# 8LedBoard.net
KiCad netlist of a schematic drawn in EAGLE
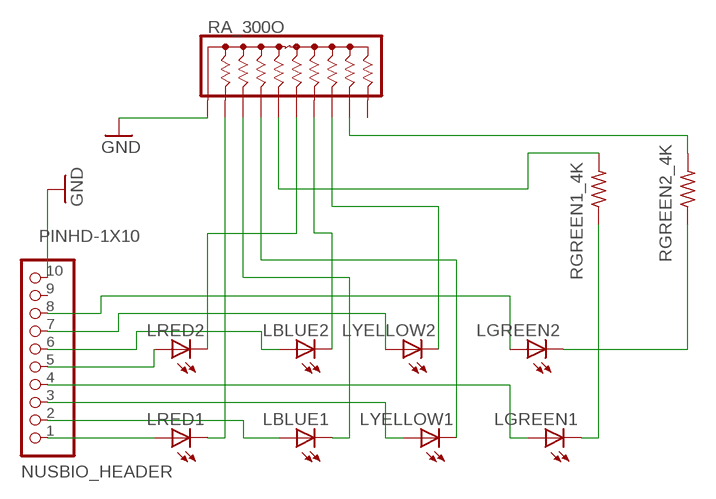
[diagram p0: schematic, sheet 1]

(export (version "E")
  (design (tool "Eeschema 10.0.6"))
  (components
    (comp (ref "LBLUE1")
      (value "LED5MM")
      (footprint "eagle-import:LED5MM")
      (libsource (lib "eagle-import") (part "LED5MM"))
    )
    (comp (ref "LBLUE2")
      (value "LED5MM")
      (footprint "eagle-import:LED5MM")
      (libsource (lib "eagle-import") (part "LED5MM"))
    )
    (comp (ref "LGREEN1")
      (value "LED5MM")
      (footprint "eagle-import:LED5MM")
      (libsource (lib "eagle-import") (part "LED5MM"))
    )
    (comp (ref "LGREEN2")
      (value "LED5MM")
      (footprint "eagle-import:LED5MM")
      (libsource (lib "eagle-import") (part "LED5MM"))
    )
    (comp (ref "LRED1")
      (value "LED5MM")
      (footprint "eagle-import:LED5MM")
      (libsource (lib "eagle-import") (part "LED5MM"))
    )
    (comp (ref "LRED2")
      (value "LED5MM")
      (footprint "eagle-import:LED5MM")
      (libsource (lib "eagle-import") (part "LED5MM"))
    )
    (comp (ref "LYELLOW1")
      (value "LED5MM")
      (footprint "eagle-import:LED5MM")
      (libsource (lib "eagle-import") (part "LED5MM"))
    )
    (comp (ref "LYELLOW2")
      (value "LED5MM")
      (footprint "eagle-import:LED5MM")
      (libsource (lib "eagle-import") (part "LED5MM"))
    )
    (comp (ref "NUSBIO_HEADER")
      (value "PINHD-1X10")
      (footprint "eagle-import:1X10-BIG")
      (libsource (lib "eagle-import") (part "PINHD-1X10"))
    )
    (comp (ref "RA_300O")
      (value "4610X")
      (footprint "eagle-import:SIP10")
      (libsource (lib "eagle-import") (part "4610X"))
    )
    (comp (ref "RGREEN1_4K")
      (value "R-US_0207/10")
      (footprint "eagle-import:0207_10")
      (libsource (lib "eagle-import") (part "R-US_0207/10"))
    )
    (comp (ref "RGREEN2_4K")
      (value "R-US_0207/10")
      (footprint "eagle-import:0207_10")
      (libsource (lib "eagle-import") (part "R-US_0207/10"))
    )
  )
  (nets
    (net (code "1") (name "GND") (class "Default")
      (node (ref "NUSBIO_HEADER") (pin "10") (pinfunction "10_10") (pintype "passive"))
      (node (ref "RA_300O") (pin "1") (pinfunction "1_1") (pintype "passive"))
    )
    (net (code "2") (name "Net-(LBLUE1-C)") (class "Default")
      (node (ref "LBLUE1") (pin "K") (pinfunction "C_K") (pintype "passive"))
      (node (ref "RA_300O") (pin "3") (pinfunction "3_3") (pintype "passive"))
    )
    (net (code "3") (name "Net-(LBLUE1-PadA)") (class "Default")
      (node (ref "LBLUE1") (pin "A") (pinfunction "A_A") (pintype "passive"))
      (node (ref "NUSBIO_HEADER") (pin "2") (pinfunction "2_2") (pintype "passive"))
    )
    (net (code "4") (name "Net-(LBLUE2-C)") (class "Default")
      (node (ref "LBLUE2") (pin "K") (pinfunction "C_K") (pintype "passive"))
      (node (ref "RA_300O") (pin "7") (pinfunction "7_7") (pintype "passive"))
    )
    (net (code "5") (name "Net-(LBLUE2-PadA)") (class "Default")
      (node (ref "LBLUE2") (pin "A") (pinfunction "A_A") (pintype "passive"))
      (node (ref "NUSBIO_HEADER") (pin "6") (pinfunction "6_6") (pintype "passive"))
    )
    (net (code "6") (name "Net-(LGREEN1-C)") (class "Default")
      (node (ref "LGREEN1") (pin "K") (pinfunction "C_K") (pintype "passive"))
      (node (ref "RGREEN1_4K") (pin "1") (pinfunction "1_1") (pintype "passive"))
    )
    (net (code "7") (name "Net-(LGREEN1-PadA)") (class "Default")
      (node (ref "LGREEN1") (pin "A") (pinfunction "A_A") (pintype "passive"))
      (node (ref "NUSBIO_HEADER") (pin "4") (pinfunction "4_4") (pintype "passive"))
    )
    (net (code "8") (name "Net-(LGREEN2-C)") (class "Default")
      (node (ref "LGREEN2") (pin "K") (pinfunction "C_K") (pintype "passive"))
      (node (ref "RGREEN2_4K") (pin "1") (pinfunction "1_1") (pintype "passive"))
    )
    (net (code "9") (name "Net-(LGREEN2-PadA)") (class "Default")
      (node (ref "LGREEN2") (pin "A") (pinfunction "A_A") (pintype "passive"))
      (node (ref "NUSBIO_HEADER") (pin "8") (pinfunction "8_8") (pintype "passive"))
    )
    (net (code "10") (name "Net-(LRED1-C)") (class "Default")
      (node (ref "LRED1") (pin "K") (pinfunction "C_K") (pintype "passive"))
      (node (ref "RA_300O") (pin "2") (pinfunction "2_2") (pintype "passive"))
    )
    (net (code "11") (name "Net-(LRED1-PadA)") (class "Default")
      (node (ref "LRED1") (pin "A") (pinfunction "A_A") (pintype "passive"))
      (node (ref "NUSBIO_HEADER") (pin "1") (pinfunction "1_1") (pintype "passive"))
    )
    (net (code "12") (name "Net-(LRED2-C)") (class "Default")
      (node (ref "LRED2") (pin "K") (pinfunction "C_K") (pintype "passive"))
      (node (ref "RA_300O") (pin "6") (pinfunction "6_6") (pintype "passive"))
    )
    (net (code "13") (name "Net-(LRED2-PadA)") (class "Default")
      (node (ref "LRED2") (pin "A") (pinfunction "A_A") (pintype "passive"))
      (node (ref "NUSBIO_HEADER") (pin "5") (pinfunction "5_5") (pintype "passive"))
    )
    (net (code "14") (name "Net-(LYELLOW1-C)") (class "Default")
      (node (ref "LYELLOW1") (pin "K") (pinfunction "C_K") (pintype "passive"))
      (node (ref "RA_300O") (pin "4") (pinfunction "4_4") (pintype "passive"))
    )
    (net (code "15") (name "Net-(LYELLOW1-PadA)") (class "Default")
      (node (ref "LYELLOW1") (pin "A") (pinfunction "A_A") (pintype "passive"))
      (node (ref "NUSBIO_HEADER") (pin "3") (pinfunction "3_3") (pintype "passive"))
    )
    (net (code "16") (name "Net-(LYELLOW2-C)") (class "Default")
      (node (ref "LYELLOW2") (pin "K") (pinfunction "C_K") (pintype "passive"))
      (node (ref "RA_300O") (pin "8") (pinfunction "8_8") (pintype "passive"))
    )
    (net (code "17") (name "Net-(LYELLOW2-PadA)") (class "Default")
      (node (ref "LYELLOW2") (pin "A") (pinfunction "A_A") (pintype "passive"))
      (node (ref "NUSBIO_HEADER") (pin "7") (pinfunction "7_7") (pintype "passive"))
    )
    (net (code "18") (name "Net-(RA_300O-Pad5)") (class "Default")
      (node (ref "RA_300O") (pin "5") (pinfunction "5_5") (pintype "passive"))
      (node (ref "RGREEN1_4K") (pin "2") (pinfunction "2_2") (pintype "passive"))
    )
    (net (code "19") (name "Net-(RA_300O-Pad9)") (class "Default")
      (node (ref "RA_300O") (pin "9") (pinfunction "9_9") (pintype "passive"))
      (node (ref "RGREEN2_4K") (pin "2") (pinfunction "2_2") (pintype "passive"))
    )
    (net (code "20") (name "unconnected-(NUSBIO_HEADER-Pad9)") (class "Default")
      (node (ref "NUSBIO_HEADER") (pin "9") (pinfunction "9_9") (pintype "passive"))
    )
    (net (code "21") (name "unconnected-(RA_300O-Pad10)") (class "Default")
      (node (ref "RA_300O") (pin "10") (pinfunction "10_10") (pintype "passive"))
    )
  )
)
